# untitled1.net
KiCad netlist of a schematic drawn in EAGLE
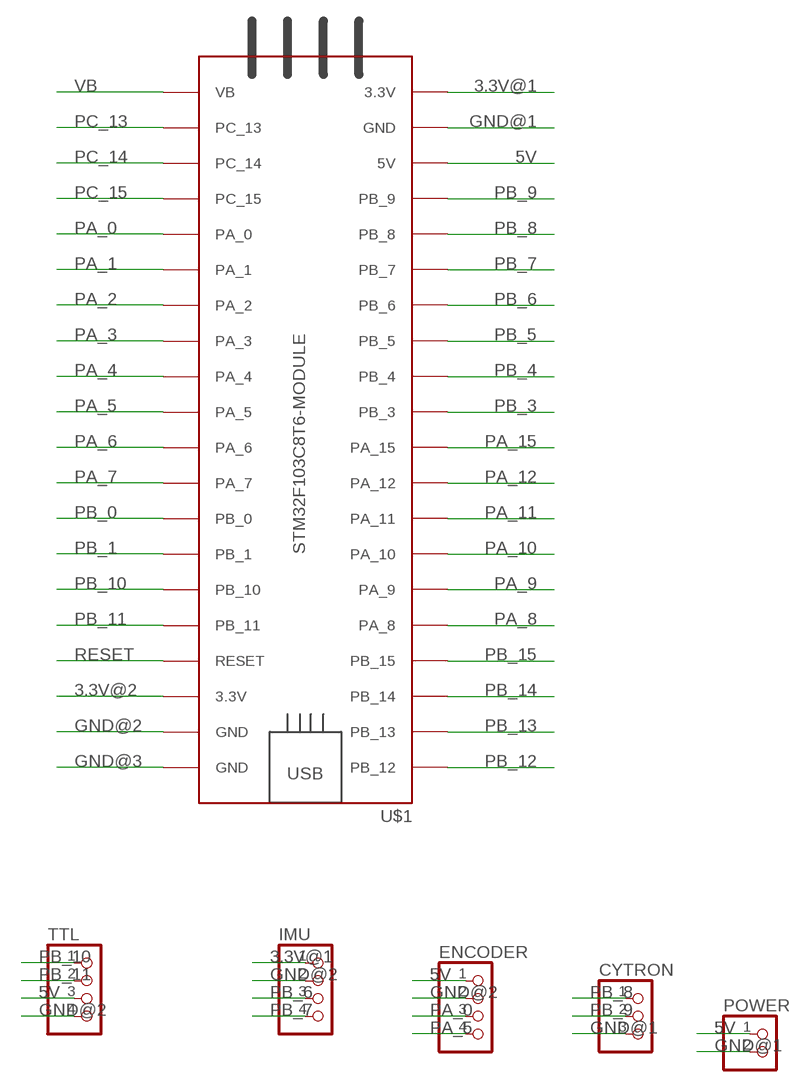
[diagram p0: schematic, sheet 1]

(export (version "E")
  (design (tool "Eeschema 10.0.6"))
  (components
    (comp (ref "CYTRON")
      (value "PINHD-1X3")
      (footprint "eagle-import:1X03")
      (libsource (lib "eagle-import") (part "PINHD-1X3"))
    )
    (comp (ref "ENCODER")
      (value "PINHD-1X4")
      (footprint "eagle-import:1X04")
      (libsource (lib "eagle-import") (part "PINHD-1X4"))
    )
    (comp (ref "IMU")
      (value "PINHD-1X4")
      (footprint "eagle-import:1X04")
      (libsource (lib "eagle-import") (part "PINHD-1X4"))
    )
    (comp (ref "POWER")
      (value "PINHD-1X2")
      (footprint "eagle-import:1X02")
      (libsource (lib "eagle-import") (part "PINHD-1X2"))
    )
    (comp (ref "TTL")
      (value "PINHD-1X4")
      (footprint "eagle-import:1X04")
      (libsource (lib "eagle-import") (part "PINHD-1X4"))
    )
    (comp (ref "U$1")
      (value "STM32F103C8T6-MODULE")
      (footprint "eagle-import:STM32F103C8T6-MODULE")
      (libsource (lib "eagle-import") (part "STM32F103C8T6-MODULE"))
    )
  )
  (nets
    (net (code "1") (name "/3.3V@1") (class "Default")
      (node (ref "IMU") (pin "1") (pinfunction "1_1") (pintype "passive"))
      (node (ref "U$1") (pin "3.3V_1") (pinfunction "3.3V_3.3V_1") (pintype "bidirectional"))
    )
    (net (code "2") (name "/3.3V@2") (class "Default")
      (node (ref "U$1") (pin "3.3V_2") (pinfunction "3.3V_3.3V_2") (pintype "bidirectional"))
    )
    (net (code "3") (name "/5V") (class "Default")
      (node (ref "ENCODER") (pin "1") (pinfunction "1_1") (pintype "passive"))
      (node (ref "POWER") (pin "1") (pinfunction "1_1") (pintype "passive"))
      (node (ref "TTL") (pin "3") (pinfunction "3_3") (pintype "passive"))
      (node (ref "U$1") (pin "5V") (pinfunction "5V_5V") (pintype "bidirectional"))
    )
    (net (code "4") (name "/GND@1") (class "Default")
      (node (ref "CYTRON") (pin "3") (pinfunction "3_3") (pintype "passive"))
      (node (ref "POWER") (pin "2") (pinfunction "2_2") (pintype "passive"))
      (node (ref "U$1") (pin "GND_1") (pinfunction "GND_GND_1") (pintype "bidirectional"))
    )
    (net (code "5") (name "/GND@2") (class "Default")
      (node (ref "ENCODER") (pin "2") (pinfunction "2_2") (pintype "passive"))
      (node (ref "IMU") (pin "2") (pinfunction "2_2") (pintype "passive"))
      (node (ref "TTL") (pin "4") (pinfunction "4_4") (pintype "passive"))
      (node (ref "U$1") (pin "GND_2") (pinfunction "GND_GND_2") (pintype "bidirectional"))
    )
    (net (code "6") (name "/GND@3") (class "Default")
      (node (ref "U$1") (pin "GND_3") (pinfunction "GND_GND_3") (pintype "power_in"))
    )
    (net (code "7") (name "/PA_0") (class "Default")
      (node (ref "ENCODER") (pin "3") (pinfunction "3_3") (pintype "passive"))
      (node (ref "U$1") (pin "PA_0") (pinfunction "PA_0_PA_0") (pintype "bidirectional"))
    )
    (net (code "8") (name "/PA_1") (class "Default")
      (node (ref "U$1") (pin "PA_1") (pinfunction "PA_1_PA_1") (pintype "bidirectional"))
    )
    (net (code "9") (name "/PA_2") (class "Default")
      (node (ref "U$1") (pin "PA_2") (pinfunction "PA_2_PA_2") (pintype "bidirectional"))
    )
    (net (code "10") (name "/PA_3") (class "Default")
      (node (ref "U$1") (pin "PA_3") (pinfunction "PA_3_PA_3") (pintype "bidirectional"))
    )
    (net (code "11") (name "/PA_4") (class "Default")
      (node (ref "U$1") (pin "PA_4") (pinfunction "PA_4_PA_4") (pintype "bidirectional"))
    )
    (net (code "12") (name "/PA_5") (class "Default")
      (node (ref "ENCODER") (pin "4") (pinfunction "4_4") (pintype "passive"))
      (node (ref "U$1") (pin "PA_5") (pinfunction "PA_5_PA_5") (pintype "bidirectional"))
    )
    (net (code "13") (name "/PA_6") (class "Default")
      (node (ref "U$1") (pin "PA_6") (pinfunction "PA_6_PA_6") (pintype "bidirectional"))
    )
    (net (code "14") (name "/PA_7") (class "Default")
      (node (ref "U$1") (pin "PA_7") (pinfunction "PA_7_PA_7") (pintype "bidirectional"))
    )
    (net (code "15") (name "/PA_8") (class "Default")
      (node (ref "U$1") (pin "PA_8") (pinfunction "PA_8_PA_8") (pintype "bidirectional"))
    )
    (net (code "16") (name "/PA_9") (class "Default")
      (node (ref "U$1") (pin "PA_9") (pinfunction "PA_9_PA_9") (pintype "bidirectional"))
    )
    (net (code "17") (name "/PA_10") (class "Default")
      (node (ref "U$1") (pin "PA_10") (pinfunction "PA_10_PA_10") (pintype "bidirectional"))
    )
    (net (code "18") (name "/PA_11") (class "Default")
      (node (ref "U$1") (pin "PA_11") (pinfunction "PA_11_PA_11") (pintype "bidirectional"))
    )
    (net (code "19") (name "/PA_12") (class "Default")
      (node (ref "U$1") (pin "PA_12") (pinfunction "PA_12_PA_12") (pintype "bidirectional"))
    )
    (net (code "20") (name "/PA_15") (class "Default")
      (node (ref "U$1") (pin "PA_15") (pinfunction "PA_15_PA_15") (pintype "bidirectional"))
    )
    (net (code "21") (name "/PB_0") (class "Default")
      (node (ref "U$1") (pin "PB_0") (pinfunction "PB_0_PB_0") (pintype "bidirectional"))
    )
    (net (code "22") (name "/PB_1") (class "Default")
      (node (ref "U$1") (pin "PB_1") (pinfunction "PB_1_PB_1") (pintype "bidirectional"))
    )
    (net (code "23") (name "/PB_3") (class "Default")
      (node (ref "U$1") (pin "PB_3") (pinfunction "PB_3_PB_3") (pintype "bidirectional"))
    )
    (net (code "24") (name "/PB_4") (class "Default")
      (node (ref "U$1") (pin "PB_4") (pinfunction "PB_4_PB_4") (pintype "bidirectional"))
    )
    (net (code "25") (name "/PB_5") (class "Default")
      (node (ref "U$1") (pin "PB_5") (pinfunction "PB_5_PB_5") (pintype "bidirectional"))
    )
    (net (code "26") (name "/PB_6") (class "Default")
      (node (ref "IMU") (pin "3") (pinfunction "3_3") (pintype "passive"))
      (node (ref "U$1") (pin "PB_6") (pinfunction "PB_6_PB_6") (pintype "bidirectional"))
    )
    (net (code "27") (name "/PB_7") (class "Default")
      (node (ref "IMU") (pin "4") (pinfunction "4_4") (pintype "passive"))
      (node (ref "U$1") (pin "PB_7") (pinfunction "PB_7_PB_7") (pintype "bidirectional"))
    )
    (net (code "28") (name "/PB_8") (class "Default")
      (node (ref "CYTRON") (pin "1") (pinfunction "1_1") (pintype "passive"))
      (node (ref "U$1") (pin "PB_8") (pinfunction "PB_8_PB_8") (pintype "bidirectional"))
    )
    (net (code "29") (name "/PB_9") (class "Default")
      (node (ref "CYTRON") (pin "2") (pinfunction "2_2") (pintype "passive"))
      (node (ref "U$1") (pin "PB_9") (pinfunction "PB_9_PB_9") (pintype "bidirectional"))
    )
    (net (code "30") (name "/PB_10") (class "Default")
      (node (ref "TTL") (pin "1") (pinfunction "1_1") (pintype "passive"))
      (node (ref "U$1") (pin "PB_10") (pinfunction "PB_10_PB_10") (pintype "bidirectional"))
    )
    (net (code "31") (name "/PB_11") (class "Default")
      (node (ref "TTL") (pin "2") (pinfunction "2_2") (pintype "passive"))
      (node (ref "U$1") (pin "PB_11") (pinfunction "PB_11_PB_11") (pintype "bidirectional"))
    )
    (net (code "32") (name "/PB_12") (class "Default")
      (node (ref "U$1") (pin "PB_12") (pinfunction "PB_12_PB_12") (pintype "bidirectional"))
    )
    (net (code "33") (name "/PB_13") (class "Default")
      (node (ref "U$1") (pin "PB_13") (pinfunction "PB_13_PB_13") (pintype "bidirectional"))
    )
    (net (code "34") (name "/PB_14") (class "Default")
      (node (ref "U$1") (pin "PB_14") (pinfunction "PB_14_PB_14") (pintype "bidirectional"))
    )
    (net (code "35") (name "/PB_15") (class "Default")
      (node (ref "U$1") (pin "PB_15") (pinfunction "PB_15_PB_15") (pintype "bidirectional"))
    )
    (net (code "36") (name "/PC_13") (class "Default")
      (node (ref "U$1") (pin "PC_13") (pinfunction "PC_13_PC_13") (pintype "bidirectional"))
    )
    (net (code "37") (name "/PC_14") (class "Default")
      (node (ref "U$1") (pin "PC_14") (pinfunction "PC_14_PC_14") (pintype "bidirectional"))
    )
    (net (code "38") (name "/PC_15") (class "Default")
      (node (ref "U$1") (pin "PC_15") (pinfunction "PC_15_PC_15") (pintype "bidirectional"))
    )
    (net (code "39") (name "/RESET") (class "Default")
      (node (ref "U$1") (pin "RESET") (pinfunction "RESET_RESET") (pintype "bidirectional"))
    )
    (net (code "40") (name "/VB") (class "Default")
      (node (ref "U$1") (pin "VB") (pinfunction "VB_VB") (pintype "bidirectional"))
    )
  )
)
